# cube-esp32-c6-easyeda-sch.net
KiCad netlist of a schematic drawn in EasyEDA
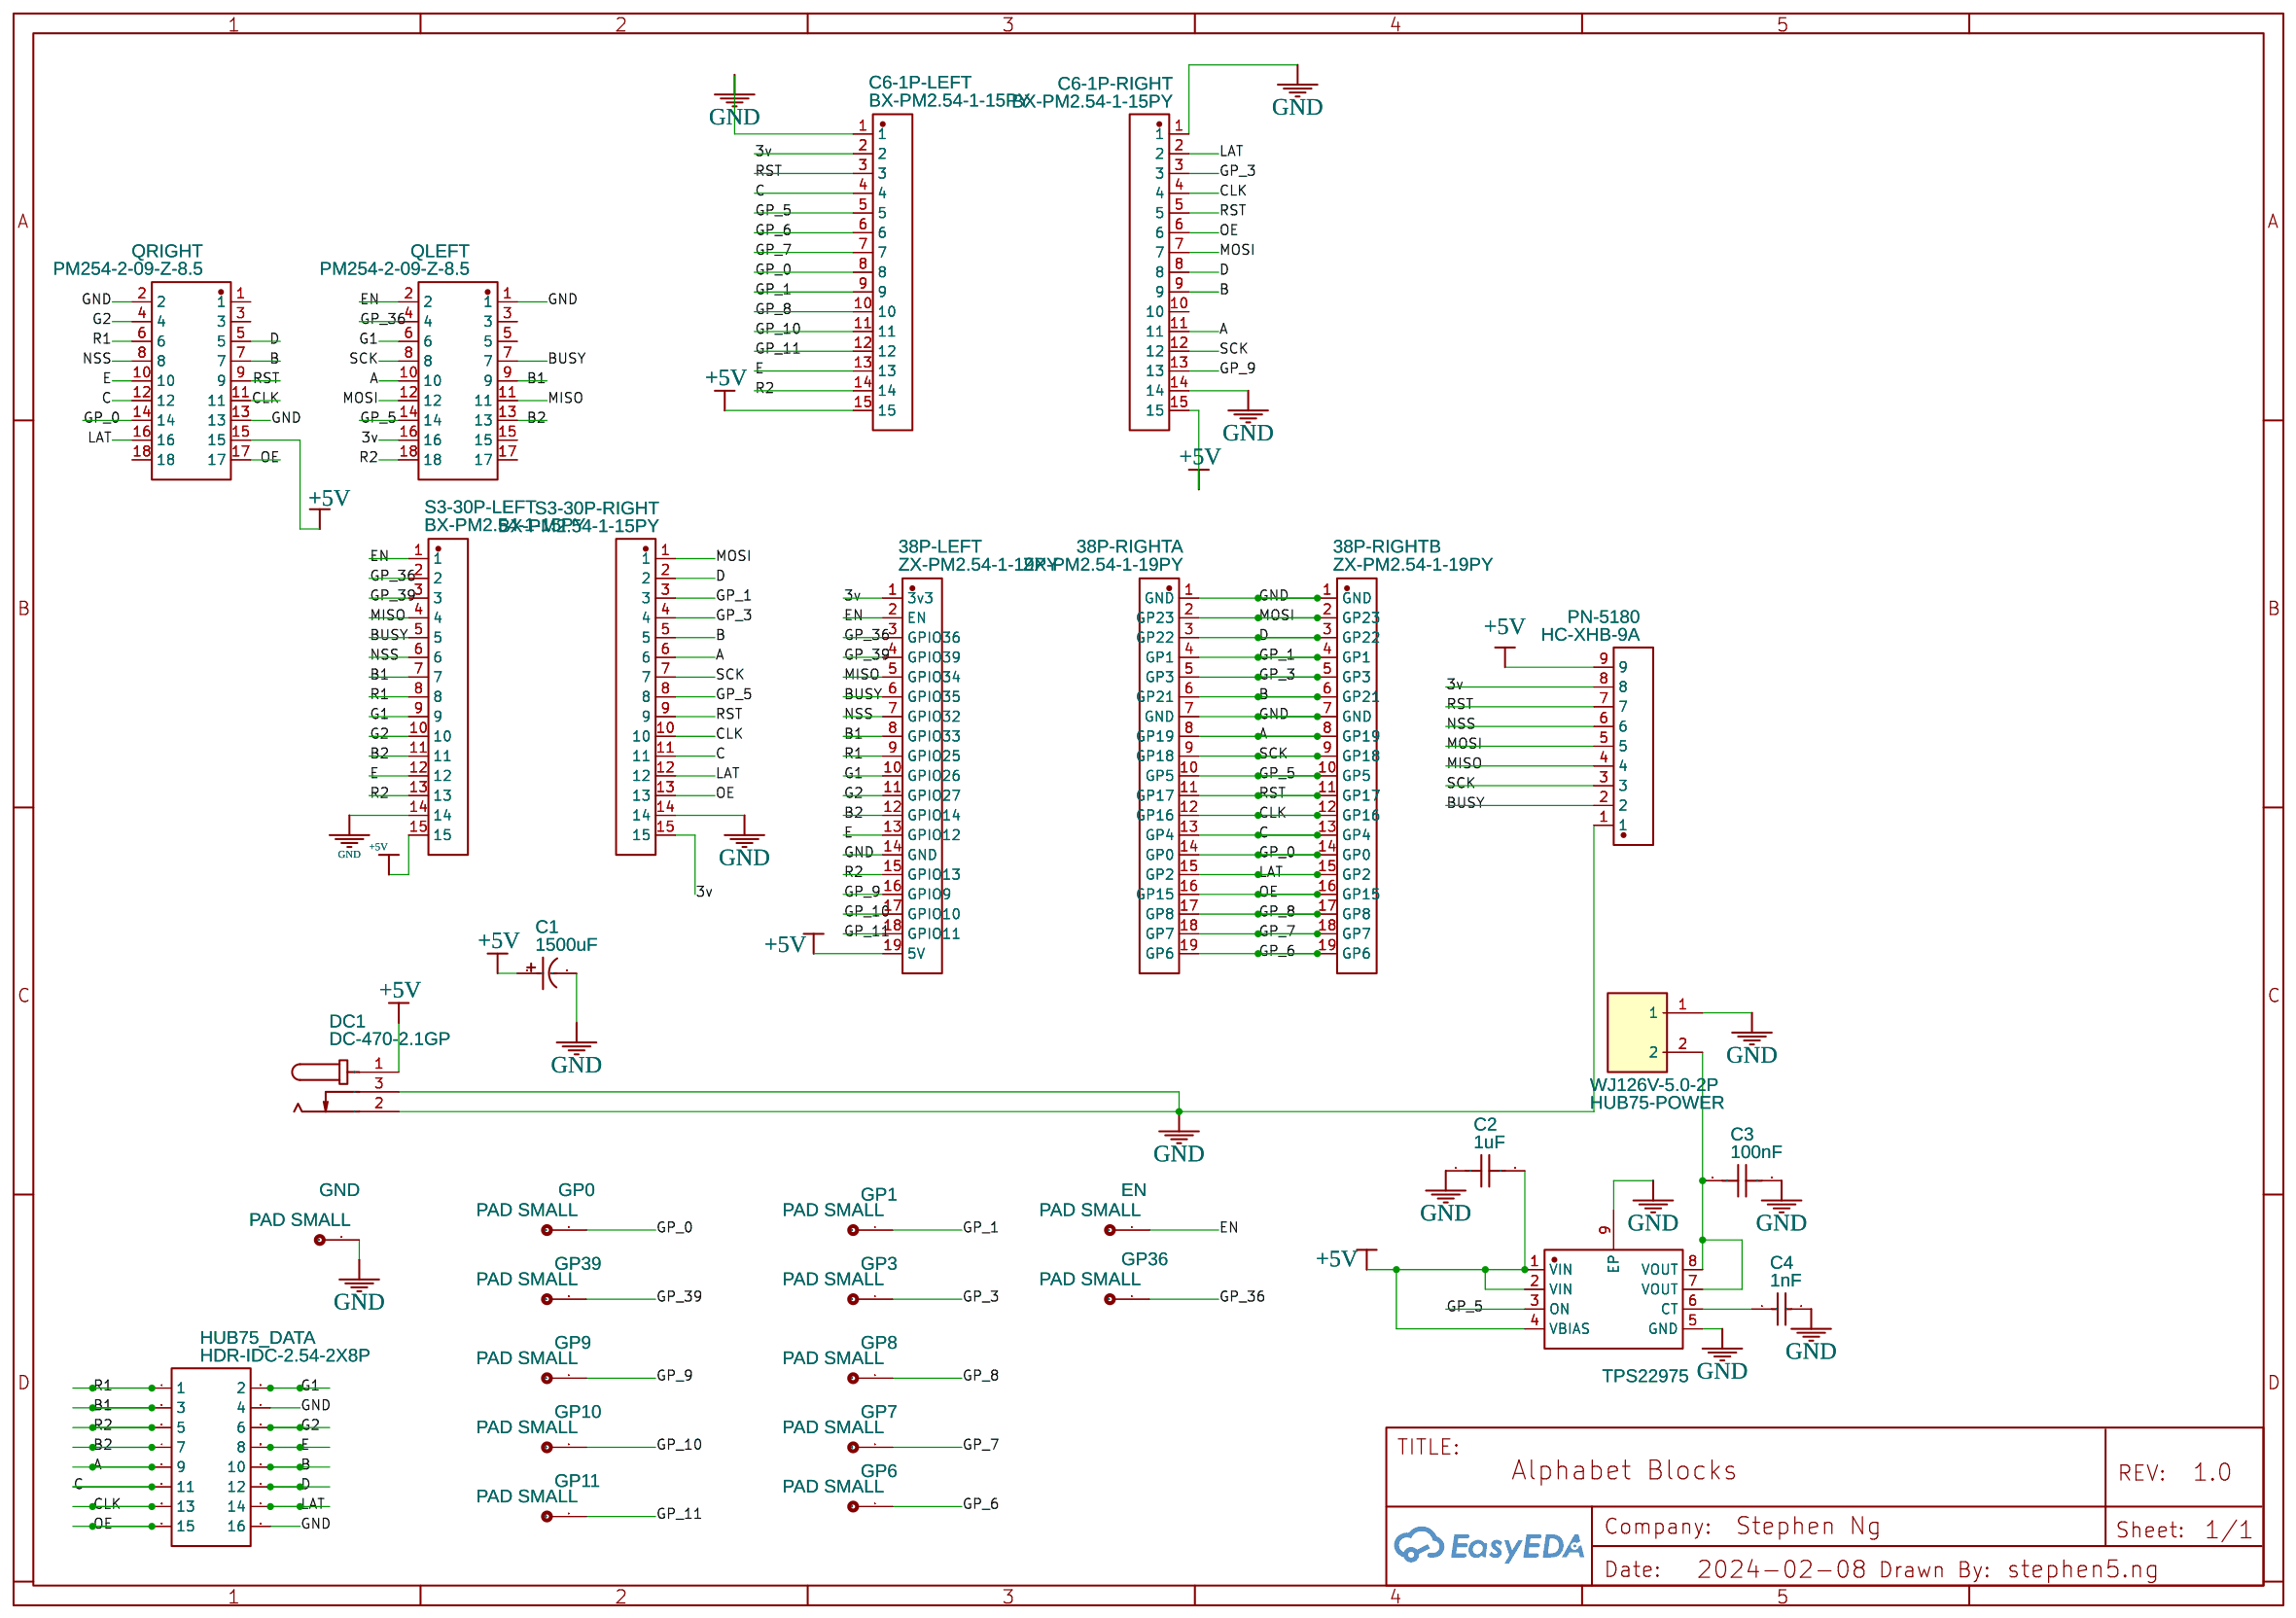
[diagram p0: schematic sheet]

(export (version "E")
  (design (tool "Eeschema 10.0.6"))
  (components
    (comp (ref "38P-LEFT")
      (value "ZX-PM2.54-1-19PY")
      (fields (field (name "Manufacturer") "Megastar(兆星)"))
      (libsource (lib "") (part "ZX-PM2.54-1-19PY_2"))
    )
    (comp (ref "38P-RIGHTA")
      (value "ZX-PM2.54-1-19PY")
      (fields (field (name "Manufacturer") "Megastar(兆星)"))
      (libsource (lib "") (part "ZX-PM2.54-1-19PY"))
    )
    (comp (ref "38P-RIGHTB")
      (value "ZX-PM2.54-1-19PY")
      (fields (field (name "Manufacturer") "Megastar(兆星)"))
      (libsource (lib "") (part "ZX-PM2.54-1-19PY_1"))
    )
    (comp (ref "C1") (value "1500uF") (libsource (lib "") (part "16ZLH1500MEFC10X20")))
    (comp (ref "C2")
      (value "1uF")
      (fields
        (field (name "Manufacturer Part") "CL05A105KA5NQNC")
        (field (name "Manufacturer") "SAMSUNG(三星)")
      )
      (libsource (lib "") (part "CL05A105KA5NQNC"))
    )
    (comp (ref "C3")
      (value "100nF")
      (fields
        (field (name "Manufacturer Part") "CL05B104KO5NNNC")
        (field (name "Manufacturer") "SAMSUNG(三星)")
      )
      (libsource (lib "") (part "CL05B104KO5NNNC"))
    )
    (comp (ref "C4")
      (value "1nF")
      (fields (field (name "Manufacturer Part") "0402B102K500NT") (field (name "Manufacturer") "FH(风华)"))
      (libsource (lib "") (part "0402B102K500NT"))
    )
    (comp (ref "C6-1P-LEFT")
      (value "BX-PM2.54-1-15PY")
      (fields (field (name "Manufacturer") "Bossie(博锡)"))
      (libsource (lib "") (part "BX-PM2.54-1-15PY_3"))
    )
    (comp (ref "C6-1P-RIGHT")
      (value "BX-PM2.54-1-15PY")
      (fields (field (name "Manufacturer") "Bossie(博锡)"))
      (libsource (lib "") (part "BX-PM2.54-1-15PY"))
    )
    (comp (ref "DC1")
      (value "DC-470-2.1GP")
      (fields (field (name "Manufacturer") "GANGYUAN(港源)"))
      (libsource (lib "") (part "DC-470-2.1GP"))
    )
    (comp (ref "EN") (value "PAD SMALL") (libsource (lib "") (part "PAD SMALL_1")))
    (comp (ref "GND") (value "PAD SMALL") (libsource (lib "") (part "PAD SMALL_2")))
    (comp (ref "GP0") (value "PAD SMALL") (libsource (lib "") (part "PAD SMALL")))
    (comp (ref "GP1") (value "PAD SMALL") (libsource (lib "") (part "PAD SMALL")))
    (comp (ref "GP3") (value "PAD SMALL") (libsource (lib "") (part "PAD SMALL")))
    (comp (ref "GP6") (value "PAD SMALL") (libsource (lib "") (part "PAD SMALL")))
    (comp (ref "GP7") (value "PAD SMALL") (libsource (lib "") (part "PAD SMALL")))
    (comp (ref "GP8") (value "PAD SMALL") (libsource (lib "") (part "PAD SMALL")))
    (comp (ref "GP9") (value "PAD SMALL") (libsource (lib "") (part "PAD SMALL")))
    (comp (ref "GP10") (value "PAD SMALL") (libsource (lib "") (part "PAD SMALL")))
    (comp (ref "GP11") (value "PAD SMALL") (libsource (lib "") (part "PAD SMALL")))
    (comp (ref "GP36") (value "PAD SMALL") (libsource (lib "") (part "PAD SMALL")))
    (comp (ref "GP39") (value "PAD SMALL") (libsource (lib "") (part "PAD SMALL")))
    (comp (ref "HUB75-POWER")
      (value "WJ126V-5.0-2P")
      (fields (field (name "Manufacturer") "KANGNEX(康奈克斯电气)"))
      (libsource (lib "") (part "WJ126V-5.0-2P"))
    )
    (comp (ref "HUB75_DATA")
      (value "HDR-IDC-2.54-2X8P")
      (fields (field (name "Manufacturer Part") "2.54-2*8P简牛") (field (name "Manufacturer") "BOOMELE(博穆精密)"))
      (libsource (lib "") (part "HDR-IDC-2.54-2X8P"))
    )
    (comp (ref "PN-5180")
      (value "HC-XHB-9A")
      (fields (field (name "Manufacturer") "HCTL(华灿天禄)"))
      (libsource (lib "") (part "HC-XHB-9A"))
    )
    (comp (ref "QLEFT")
      (value "PM254-2-09-Z-8.5")
      (fields (field (name "Manufacturer") "HCTL(华灿天禄)"))
      (libsource (lib "") (part "PM254-2-09-Z-8.5"))
    )
    (comp (ref "QRIGHT")
      (value "PM254-2-09-Z-8.5")
      (fields (field (name "Manufacturer") "HCTL(华灿天禄)"))
      (libsource (lib "") (part "PM254-2-09-Z-8.5_1"))
    )
    (comp (ref "S")
      (value "TPS22975")
      (fields (field (name "Manufacturer Part") "TPS22975DSGR") (field (name "Manufacturer") "TI(德州仪器)"))
      (libsource (lib "") (part "TPS22975DSGR"))
    )
    (comp (ref "S3-30P-LEFT")
      (value "BX-PM2.54-1-15PY")
      (fields (field (name "Manufacturer") "Bossie(博锡)"))
      (libsource (lib "") (part "BX-PM2.54-1-15PY_2"))
    )
    (comp (ref "S3-30P-RIGHT")
      (value "BX-PM2.54-1-15PY")
      (fields (field (name "Manufacturer") "Bossie(博锡)"))
      (libsource (lib "") (part "BX-PM2.54-1-15PY_1"))
    )
  )
  (nets
    (net (code "1") (name "+5V") (class "Default")
      (node (ref "38P-LEFT") (pin "19") (pinfunction "5V_19") (pintype "unspecified"))
      (node (ref "C1") (pin "1") (pinfunction "1_1") (pintype "input"))
      (node (ref "C2") (pin "2") (pinfunction "2_2") (pintype "unspecified"))
      (node (ref "C6-1P-LEFT") (pin "15") (pinfunction "15_15") (pintype "unspecified"))
      (node (ref "C6-1P-RIGHT") (pin "15") (pinfunction "15_15") (pintype "unspecified"))
      (node (ref "DC1") (pin "1") (pinfunction "1_1") (pintype "unspecified"))
      (node (ref "PN-5180") (pin "9") (pinfunction "9_9") (pintype "unspecified"))
      (node (ref "QRIGHT") (pin "15") (pinfunction "15_15") (pintype "unspecified"))
      (node (ref "S") (pin "1") (pinfunction "VIN_1") (pintype "unspecified"))
      (node (ref "S") (pin "2") (pinfunction "VIN_2") (pintype "unspecified"))
      (node (ref "S") (pin "4") (pinfunction "VBIAS_4") (pintype "unspecified"))
      (node (ref "S3-30P-LEFT") (pin "15") (pinfunction "15_15") (pintype "unspecified"))
    )
    (net (code "2") (name "/3v") (class "Default")
      (node (ref "38P-LEFT") (pin "1") (pinfunction "3v3_1") (pintype "unspecified"))
      (node (ref "C6-1P-LEFT") (pin "2") (pinfunction "2_2") (pintype "unspecified"))
      (node (ref "PN-5180") (pin "8") (pinfunction "8_8") (pintype "unspecified"))
      (node (ref "QLEFT") (pin "16") (pinfunction "16_16") (pintype "unspecified"))
      (node (ref "S3-30P-RIGHT") (pin "15") (pinfunction "15_15") (pintype "unspecified"))
    )
    (net (code "3") (name "/A") (class "Default")
      (node (ref "38P-RIGHTA") (pin "8") (pinfunction "GP19_8") (pintype "unspecified"))
      (node (ref "38P-RIGHTB") (pin "8") (pinfunction "GP19_8") (pintype "unspecified"))
      (node (ref "C6-1P-RIGHT") (pin "11") (pinfunction "11_11") (pintype "unspecified"))
      (node (ref "HUB75_DATA") (pin "9") (pinfunction "9_9") (pintype "unspecified"))
      (node (ref "QLEFT") (pin "10") (pinfunction "10_10") (pintype "unspecified"))
      (node (ref "S3-30P-RIGHT") (pin "6") (pinfunction "6_6") (pintype "unspecified"))
    )
    (net (code "4") (name "/B") (class "Default")
      (node (ref "38P-RIGHTA") (pin "6") (pinfunction "GP21_6") (pintype "unspecified"))
      (node (ref "38P-RIGHTB") (pin "6") (pinfunction "GP21_6") (pintype "unspecified"))
      (node (ref "C6-1P-RIGHT") (pin "9") (pinfunction "9_9") (pintype "unspecified"))
      (node (ref "HUB75_DATA") (pin "10") (pinfunction "10_10") (pintype "unspecified"))
      (node (ref "QRIGHT") (pin "7") (pinfunction "7_7") (pintype "unspecified"))
      (node (ref "S3-30P-RIGHT") (pin "5") (pinfunction "5_5") (pintype "unspecified"))
    )
    (net (code "5") (name "/B1") (class "Default")
      (node (ref "38P-LEFT") (pin "8") (pinfunction "GPIO33_8") (pintype "unspecified"))
      (node (ref "HUB75_DATA") (pin "3") (pinfunction "3_3") (pintype "unspecified"))
      (node (ref "QLEFT") (pin "9") (pinfunction "9_9") (pintype "unspecified"))
      (node (ref "S3-30P-LEFT") (pin "7") (pinfunction "7_7") (pintype "unspecified"))
    )
    (net (code "6") (name "/B2") (class "Default")
      (node (ref "38P-LEFT") (pin "12") (pinfunction "GPIO14_12") (pintype "unspecified"))
      (node (ref "HUB75_DATA") (pin "7") (pinfunction "7_7") (pintype "unspecified"))
      (node (ref "QLEFT") (pin "13") (pinfunction "13_13") (pintype "unspecified"))
      (node (ref "S3-30P-LEFT") (pin "11") (pinfunction "11_11") (pintype "unspecified"))
    )
    (net (code "7") (name "/BUSY") (class "Default")
      (node (ref "38P-LEFT") (pin "6") (pinfunction "GPIO35_6") (pintype "unspecified"))
      (node (ref "PN-5180") (pin "2") (pinfunction "2_2") (pintype "unspecified"))
      (node (ref "QLEFT") (pin "7") (pinfunction "7_7") (pintype "unspecified"))
      (node (ref "S3-30P-LEFT") (pin "5") (pinfunction "5_5") (pintype "unspecified"))
    )
    (net (code "8") (name "/C") (class "Default")
      (node (ref "38P-RIGHTA") (pin "13") (pinfunction "GP4_13") (pintype "unspecified"))
      (node (ref "38P-RIGHTB") (pin "13") (pinfunction "GP4_13") (pintype "unspecified"))
      (node (ref "C6-1P-LEFT") (pin "4") (pinfunction "4_4") (pintype "unspecified"))
      (node (ref "HUB75_DATA") (pin "11") (pinfunction "11_11") (pintype "unspecified"))
      (node (ref "QRIGHT") (pin "12") (pinfunction "12_12") (pintype "unspecified"))
      (node (ref "S3-30P-RIGHT") (pin "11") (pinfunction "11_11") (pintype "unspecified"))
    )
    (net (code "9") (name "/CLK") (class "Default")
      (node (ref "38P-RIGHTA") (pin "12") (pinfunction "GP16_12") (pintype "unspecified"))
      (node (ref "38P-RIGHTB") (pin "12") (pinfunction "GP16_12") (pintype "unspecified"))
      (node (ref "C6-1P-RIGHT") (pin "4") (pinfunction "4_4") (pintype "unspecified"))
      (node (ref "HUB75_DATA") (pin "13") (pinfunction "13_13") (pintype "unspecified"))
      (node (ref "QRIGHT") (pin "11") (pinfunction "11_11") (pintype "unspecified"))
      (node (ref "S3-30P-RIGHT") (pin "10") (pinfunction "10_10") (pintype "unspecified"))
    )
    (net (code "10") (name "/D") (class "Default")
      (node (ref "38P-RIGHTA") (pin "3") (pinfunction "GP22_3") (pintype "unspecified"))
      (node (ref "38P-RIGHTB") (pin "3") (pinfunction "GP22_3") (pintype "unspecified"))
      (node (ref "C6-1P-RIGHT") (pin "8") (pinfunction "8_8") (pintype "unspecified"))
      (node (ref "HUB75_DATA") (pin "12") (pinfunction "12_12") (pintype "unspecified"))
      (node (ref "QRIGHT") (pin "5") (pinfunction "5_5") (pintype "unspecified"))
      (node (ref "S3-30P-RIGHT") (pin "2") (pinfunction "2_2") (pintype "unspecified"))
    )
    (net (code "11") (name "/E") (class "Default")
      (node (ref "38P-LEFT") (pin "13") (pinfunction "GPIO12_13") (pintype "unspecified"))
      (node (ref "C6-1P-LEFT") (pin "13") (pinfunction "13_13") (pintype "unspecified"))
      (node (ref "HUB75_DATA") (pin "8") (pinfunction "8_8") (pintype "unspecified"))
      (node (ref "QRIGHT") (pin "10") (pinfunction "10_10") (pintype "unspecified"))
      (node (ref "S3-30P-LEFT") (pin "12") (pinfunction "12_12") (pintype "unspecified"))
    )
    (net (code "12") (name "/EN") (class "Default")
      (node (ref "38P-LEFT") (pin "2") (pinfunction "EN_2") (pintype "unspecified"))
      (node (ref "EN") (pin "1") (pinfunction "Pad_1") (pintype "unspecified"))
      (node (ref "QLEFT") (pin "2") (pinfunction "2_2") (pintype "unspecified"))
      (node (ref "S3-30P-LEFT") (pin "1") (pinfunction "1_1") (pintype "unspecified"))
    )
    (net (code "13") (name "/G1") (class "Default")
      (node (ref "38P-LEFT") (pin "10") (pinfunction "GPIO26_10") (pintype "unspecified"))
      (node (ref "HUB75_DATA") (pin "2") (pinfunction "2_2") (pintype "unspecified"))
      (node (ref "QLEFT") (pin "6") (pinfunction "6_6") (pintype "unspecified"))
      (node (ref "S3-30P-LEFT") (pin "9") (pinfunction "9_9") (pintype "unspecified"))
    )
    (net (code "14") (name "/G2") (class "Default")
      (node (ref "38P-LEFT") (pin "11") (pinfunction "GPIO27_11") (pintype "unspecified"))
      (node (ref "HUB75_DATA") (pin "6") (pinfunction "6_6") (pintype "unspecified"))
      (node (ref "QRIGHT") (pin "4") (pinfunction "4_4") (pintype "unspecified"))
      (node (ref "S3-30P-LEFT") (pin "10") (pinfunction "10_10") (pintype "unspecified"))
    )
    (net (code "15") (name "/GP_0") (class "Default")
      (node (ref "38P-RIGHTA") (pin "14") (pinfunction "GP0_14") (pintype "unspecified"))
      (node (ref "38P-RIGHTB") (pin "14") (pinfunction "GP0_14") (pintype "unspecified"))
      (node (ref "C6-1P-LEFT") (pin "8") (pinfunction "8_8") (pintype "unspecified"))
      (node (ref "GP0") (pin "1") (pinfunction "Pad_1") (pintype "unspecified"))
      (node (ref "QRIGHT") (pin "14") (pinfunction "14_14") (pintype "unspecified"))
    )
    (net (code "16") (name "/GP_1") (class "Default")
      (node (ref "38P-RIGHTA") (pin "4") (pinfunction "GP1_4") (pintype "unspecified"))
      (node (ref "38P-RIGHTB") (pin "4") (pinfunction "GP1_4") (pintype "unspecified"))
      (node (ref "C6-1P-LEFT") (pin "9") (pinfunction "9_9") (pintype "unspecified"))
      (node (ref "GP1") (pin "1") (pinfunction "Pad_1") (pintype "unspecified"))
      (node (ref "S3-30P-RIGHT") (pin "3") (pinfunction "3_3") (pintype "unspecified"))
    )
    (net (code "17") (name "/GP_3") (class "Default")
      (node (ref "38P-RIGHTA") (pin "5") (pinfunction "GP3_5") (pintype "unspecified"))
      (node (ref "38P-RIGHTB") (pin "5") (pinfunction "GP3_5") (pintype "unspecified"))
      (node (ref "C6-1P-RIGHT") (pin "3") (pinfunction "3_3") (pintype "unspecified"))
      (node (ref "GP3") (pin "1") (pinfunction "Pad_1") (pintype "unspecified"))
      (node (ref "S3-30P-RIGHT") (pin "4") (pinfunction "4_4") (pintype "unspecified"))
    )
    (net (code "18") (name "/GP_5") (class "Default")
      (node (ref "38P-RIGHTA") (pin "10") (pinfunction "GP5_10") (pintype "unspecified"))
      (node (ref "38P-RIGHTB") (pin "10") (pinfunction "GP5_10") (pintype "unspecified"))
      (node (ref "C6-1P-LEFT") (pin "5") (pinfunction "5_5") (pintype "unspecified"))
      (node (ref "QLEFT") (pin "14") (pinfunction "14_14") (pintype "unspecified"))
      (node (ref "S") (pin "3") (pinfunction "ON_3") (pintype "unspecified"))
      (node (ref "S3-30P-RIGHT") (pin "8") (pinfunction "8_8") (pintype "unspecified"))
    )
    (net (code "19") (name "/GP_6") (class "Default")
      (node (ref "38P-RIGHTA") (pin "19") (pinfunction "GP6_19") (pintype "unspecified"))
      (node (ref "38P-RIGHTB") (pin "19") (pinfunction "GP6_19") (pintype "unspecified"))
      (node (ref "C6-1P-LEFT") (pin "6") (pinfunction "6_6") (pintype "unspecified"))
      (node (ref "GP6") (pin "1") (pinfunction "Pad_1") (pintype "unspecified"))
    )
    (net (code "20") (name "/GP_7") (class "Default")
      (node (ref "38P-RIGHTA") (pin "18") (pinfunction "GP7_18") (pintype "unspecified"))
      (node (ref "38P-RIGHTB") (pin "18") (pinfunction "GP7_18") (pintype "unspecified"))
      (node (ref "C6-1P-LEFT") (pin "7") (pinfunction "7_7") (pintype "unspecified"))
      (node (ref "GP7") (pin "1") (pinfunction "Pad_1") (pintype "unspecified"))
    )
    (net (code "21") (name "/GP_8") (class "Default")
      (node (ref "38P-RIGHTA") (pin "17") (pinfunction "GP8_17") (pintype "unspecified"))
      (node (ref "38P-RIGHTB") (pin "17") (pinfunction "GP8_17") (pintype "unspecified"))
      (node (ref "C6-1P-LEFT") (pin "10") (pinfunction "10_10") (pintype "unspecified"))
      (node (ref "GP8") (pin "1") (pinfunction "Pad_1") (pintype "unspecified"))
    )
    (net (code "22") (name "/GP_9") (class "Default")
      (node (ref "38P-LEFT") (pin "16") (pinfunction "GPIO9_16") (pintype "unspecified"))
      (node (ref "C6-1P-RIGHT") (pin "13") (pinfunction "13_13") (pintype "unspecified"))
      (node (ref "GP9") (pin "1") (pinfunction "Pad_1") (pintype "unspecified"))
    )
    (net (code "23") (name "/GP_10") (class "Default")
      (node (ref "38P-LEFT") (pin "17") (pinfunction "GPIO10_17") (pintype "unspecified"))
      (node (ref "C6-1P-LEFT") (pin "11") (pinfunction "11_11") (pintype "unspecified"))
      (node (ref "GP10") (pin "1") (pinfunction "Pad_1") (pintype "unspecified"))
    )
    (net (code "24") (name "/GP_11") (class "Default")
      (node (ref "38P-LEFT") (pin "18") (pinfunction "GPIO11_18") (pintype "unspecified"))
      (node (ref "C6-1P-LEFT") (pin "12") (pinfunction "12_12") (pintype "unspecified"))
      (node (ref "GP11") (pin "1") (pinfunction "Pad_1") (pintype "unspecified"))
    )
    (net (code "25") (name "/GP_36") (class "Default")
      (node (ref "38P-LEFT") (pin "3") (pinfunction "GPIO36_3") (pintype "unspecified"))
      (node (ref "GP36") (pin "1") (pinfunction "Pad_1") (pintype "unspecified"))
      (node (ref "QLEFT") (pin "4") (pinfunction "4_4") (pintype "unspecified"))
      (node (ref "S3-30P-LEFT") (pin "2") (pinfunction "2_2") (pintype "unspecified"))
    )
    (net (code "26") (name "/GP_39") (class "Default")
      (node (ref "38P-LEFT") (pin "4") (pinfunction "GPIO39_4") (pintype "unspecified"))
      (node (ref "GP39") (pin "1") (pinfunction "Pad_1") (pintype "unspecified"))
      (node (ref "S3-30P-LEFT") (pin "3") (pinfunction "3_3") (pintype "unspecified"))
    )
    (net (code "27") (name "/LAT") (class "Default")
      (node (ref "38P-RIGHTA") (pin "15") (pinfunction "GP2_15") (pintype "unspecified"))
      (node (ref "38P-RIGHTB") (pin "15") (pinfunction "GP2_15") (pintype "unspecified"))
      (node (ref "C6-1P-RIGHT") (pin "2") (pinfunction "2_2") (pintype "unspecified"))
      (node (ref "HUB75_DATA") (pin "14") (pinfunction "14_14") (pintype "unspecified"))
      (node (ref "QRIGHT") (pin "16") (pinfunction "16_16") (pintype "unspecified"))
      (node (ref "S3-30P-RIGHT") (pin "12") (pinfunction "12_12") (pintype "unspecified"))
    )
    (net (code "28") (name "/MISO") (class "Default")
      (node (ref "38P-LEFT") (pin "5") (pinfunction "GPIO34_5") (pintype "unspecified"))
      (node (ref "PN-5180") (pin "4") (pinfunction "4_4") (pintype "unspecified"))
      (node (ref "QLEFT") (pin "11") (pinfunction "11_11") (pintype "unspecified"))
      (node (ref "S3-30P-LEFT") (pin "4") (pinfunction "4_4") (pintype "unspecified"))
    )
    (net (code "29") (name "/MOSI") (class "Default")
      (node (ref "38P-RIGHTA") (pin "2") (pinfunction "GP23_2") (pintype "unspecified"))
      (node (ref "38P-RIGHTB") (pin "2") (pinfunction "GP23_2") (pintype "unspecified"))
      (node (ref "C6-1P-RIGHT") (pin "7") (pinfunction "7_7") (pintype "unspecified"))
      (node (ref "PN-5180") (pin "5") (pinfunction "5_5") (pintype "unspecified"))
      (node (ref "QLEFT") (pin "12") (pinfunction "12_12") (pintype "unspecified"))
      (node (ref "S3-30P-RIGHT") (pin "1") (pinfunction "1_1") (pintype "unspecified"))
    )
    (net (code "30") (name "/NSS") (class "Default")
      (node (ref "38P-LEFT") (pin "7") (pinfunction "GPIO32_7") (pintype "unspecified"))
      (node (ref "PN-5180") (pin "6") (pinfunction "6_6") (pintype "unspecified"))
      (node (ref "QRIGHT") (pin "8") (pinfunction "8_8") (pintype "unspecified"))
      (node (ref "S3-30P-LEFT") (pin "6") (pinfunction "6_6") (pintype "unspecified"))
    )
    (net (code "31") (name "/OE") (class "Default")
      (node (ref "38P-RIGHTA") (pin "16") (pinfunction "GP15_16") (pintype "unspecified"))
      (node (ref "38P-RIGHTB") (pin "16") (pinfunction "GP15_16") (pintype "unspecified"))
      (node (ref "C6-1P-RIGHT") (pin "6") (pinfunction "6_6") (pintype "unspecified"))
      (node (ref "HUB75_DATA") (pin "15") (pinfunction "15_15") (pintype "unspecified"))
      (node (ref "QRIGHT") (pin "17") (pinfunction "17_17") (pintype "unspecified"))
      (node (ref "S3-30P-RIGHT") (pin "13") (pinfunction "13_13") (pintype "unspecified"))
    )
    (net (code "32") (name "/R1") (class "Default")
      (node (ref "38P-LEFT") (pin "9") (pinfunction "GPIO25_9") (pintype "unspecified"))
      (node (ref "HUB75_DATA") (pin "1") (pinfunction "1_1") (pintype "unspecified"))
      (node (ref "QRIGHT") (pin "6") (pinfunction "6_6") (pintype "unspecified"))
      (node (ref "S3-30P-LEFT") (pin "8") (pinfunction "8_8") (pintype "unspecified"))
    )
    (net (code "33") (name "/R2") (class "Default")
      (node (ref "38P-LEFT") (pin "15") (pinfunction "GPIO13_15") (pintype "unspecified"))
      (node (ref "C6-1P-LEFT") (pin "14") (pinfunction "14_14") (pintype "unspecified"))
      (node (ref "HUB75_DATA") (pin "5") (pinfunction "5_5") (pintype "unspecified"))
      (node (ref "QLEFT") (pin "18") (pinfunction "18_18") (pintype "unspecified"))
      (node (ref "S3-30P-LEFT") (pin "13") (pinfunction "13_13") (pintype "unspecified"))
    )
    (net (code "34") (name "/RST") (class "Default")
      (node (ref "38P-RIGHTA") (pin "11") (pinfunction "GP17_11") (pintype "unspecified"))
      (node (ref "38P-RIGHTB") (pin "11") (pinfunction "GP17_11") (pintype "unspecified"))
      (node (ref "C6-1P-LEFT") (pin "3") (pinfunction "3_3") (pintype "unspecified"))
      (node (ref "C6-1P-RIGHT") (pin "5") (pinfunction "5_5") (pintype "unspecified"))
      (node (ref "PN-5180") (pin "7") (pinfunction "7_7") (pintype "unspecified"))
      (node (ref "QRIGHT") (pin "9") (pinfunction "9_9") (pintype "unspecified"))
      (node (ref "S3-30P-RIGHT") (pin "9") (pinfunction "9_9") (pintype "unspecified"))
    )
    (net (code "35") (name "/SCK") (class "Default")
      (node (ref "38P-RIGHTA") (pin "9") (pinfunction "GP18_9") (pintype "unspecified"))
      (node (ref "38P-RIGHTB") (pin "9") (pinfunction "GP18_9") (pintype "unspecified"))
      (node (ref "C6-1P-RIGHT") (pin "12") (pinfunction "12_12") (pintype "unspecified"))
      (node (ref "PN-5180") (pin "3") (pinfunction "3_3") (pintype "unspecified"))
      (node (ref "QLEFT") (pin "8") (pinfunction "8_8") (pintype "unspecified"))
      (node (ref "S3-30P-RIGHT") (pin "7") (pinfunction "7_7") (pintype "unspecified"))
    )
    (net (code "36") (name "GND") (class "Default")
      (node (ref "38P-LEFT") (pin "14") (pinfunction "GND_14") (pintype "unspecified"))
      (node (ref "38P-RIGHTA") (pin "1") (pinfunction "GND_1") (pintype "unspecified"))
      (node (ref "38P-RIGHTA") (pin "7") (pinfunction "GND_7") (pintype "unspecified"))
      (node (ref "38P-RIGHTB") (pin "1") (pinfunction "GND_1") (pintype "unspecified"))
      (node (ref "38P-RIGHTB") (pin "7") (pinfunction "GND_7") (pintype "unspecified"))
      (node (ref "C1") (pin "2") (pinfunction "2_2") (pintype "input"))
      (node (ref "C2") (pin "1") (pinfunction "1_1") (pintype "unspecified"))
      (node (ref "C3") (pin "2") (pinfunction "2_2") (pintype "unspecified"))
      (node (ref "C4") (pin "2") (pinfunction "2_2") (pintype "input"))
      (node (ref "C6-1P-LEFT") (pin "1") (pinfunction "1_1") (pintype "unspecified"))
      (node (ref "C6-1P-RIGHT") (pin "1") (pinfunction "1_1") (pintype "unspecified"))
      (node (ref "C6-1P-RIGHT") (pin "14") (pinfunction "14_14") (pintype "unspecified"))
      (node (ref "DC1") (pin "2") (pinfunction "2_2") (pintype "unspecified"))
      (node (ref "DC1") (pin "3") (pinfunction "3_3") (pintype "unspecified"))
      (node (ref "GND") (pin "1") (pinfunction "Pad_1") (pintype "unspecified"))
      (node (ref "HUB75-POWER") (pin "1") (pinfunction "1_1") (pintype "input"))
      (node (ref "HUB75_DATA") (pin "16") (pinfunction "16_16") (pintype "unspecified"))
      (node (ref "HUB75_DATA") (pin "4") (pinfunction "4_4") (pintype "unspecified"))
      (node (ref "PN-5180") (pin "1") (pinfunction "1_1") (pintype "unspecified"))
      (node (ref "QLEFT") (pin "1") (pinfunction "1_1") (pintype "unspecified"))
      (node (ref "QRIGHT") (pin "13") (pinfunction "13_13") (pintype "unspecified"))
      (node (ref "QRIGHT") (pin "2") (pinfunction "2_2") (pintype "unspecified"))
      (node (ref "S") (pin "5") (pinfunction "GND_5") (pintype "unspecified"))
      (node (ref "S") (pin "9") (pinfunction "EP_9") (pintype "unspecified"))
      (node (ref "S3-30P-LEFT") (pin "14") (pinfunction "14_14") (pintype "unspecified"))
      (node (ref "S3-30P-RIGHT") (pin "14") (pinfunction "14_14") (pintype "unspecified"))
    )
    (net (code "37") (name "Net-(C3-Pad1)") (class "Default")
      (node (ref "C3") (pin "1") (pinfunction "1_1") (pintype "unspecified"))
      (node (ref "HUB75-POWER") (pin "2") (pinfunction "2_2") (pintype "input"))
      (node (ref "S") (pin "7") (pinfunction "VOUT_7") (pintype "unspecified"))
      (node (ref "S") (pin "8") (pinfunction "VOUT_8") (pintype "unspecified"))
    )
    (net (code "38") (name "Net-(S-CT)") (class "Default")
      (node (ref "C4") (pin "1") (pinfunction "1_1") (pintype "input"))
      (node (ref "S") (pin "6") (pinfunction "CT_6") (pintype "unspecified"))
    )
    (net (code "39") (name "unconnected-(C6-1P-RIGHT-Pad10)") (class "Default")
      (node (ref "C6-1P-RIGHT") (pin "10") (pinfunction "10_10") (pintype "unspecified"))
    )
    (net (code "40") (name "unconnected-(QLEFT-Pad3)") (class "Default")
      (node (ref "QLEFT") (pin "3") (pinfunction "3_3") (pintype "unspecified"))
    )
    (net (code "41") (name "unconnected-(QLEFT-Pad5)") (class "Default")
      (node (ref "QLEFT") (pin "5") (pinfunction "5_5") (pintype "unspecified"))
    )
    (net (code "42") (name "unconnected-(QLEFT-Pad15)") (class "Default")
      (node (ref "QLEFT") (pin "15") (pinfunction "15_15") (pintype "unspecified"))
    )
    (net (code "43") (name "unconnected-(QLEFT-Pad17)") (class "Default")
      (node (ref "QLEFT") (pin "17") (pinfunction "17_17") (pintype "unspecified"))
    )
    (net (code "44") (name "unconnected-(QRIGHT-Pad1)") (class "Default")
      (node (ref "QRIGHT") (pin "1") (pinfunction "1_1") (pintype "unspecified"))
    )
    (net (code "45") (name "unconnected-(QRIGHT-Pad3)") (class "Default")
      (node (ref "QRIGHT") (pin "3") (pinfunction "3_3") (pintype "unspecified"))
    )
    (net (code "46") (name "unconnected-(QRIGHT-Pad18)") (class "Default")
      (node (ref "QRIGHT") (pin "18") (pinfunction "18_18") (pintype "unspecified"))
    )
  )
)
